# OnOnfre_DevBoard_rev4.net
KiCad netlist of a schematic drawn in EAGLE
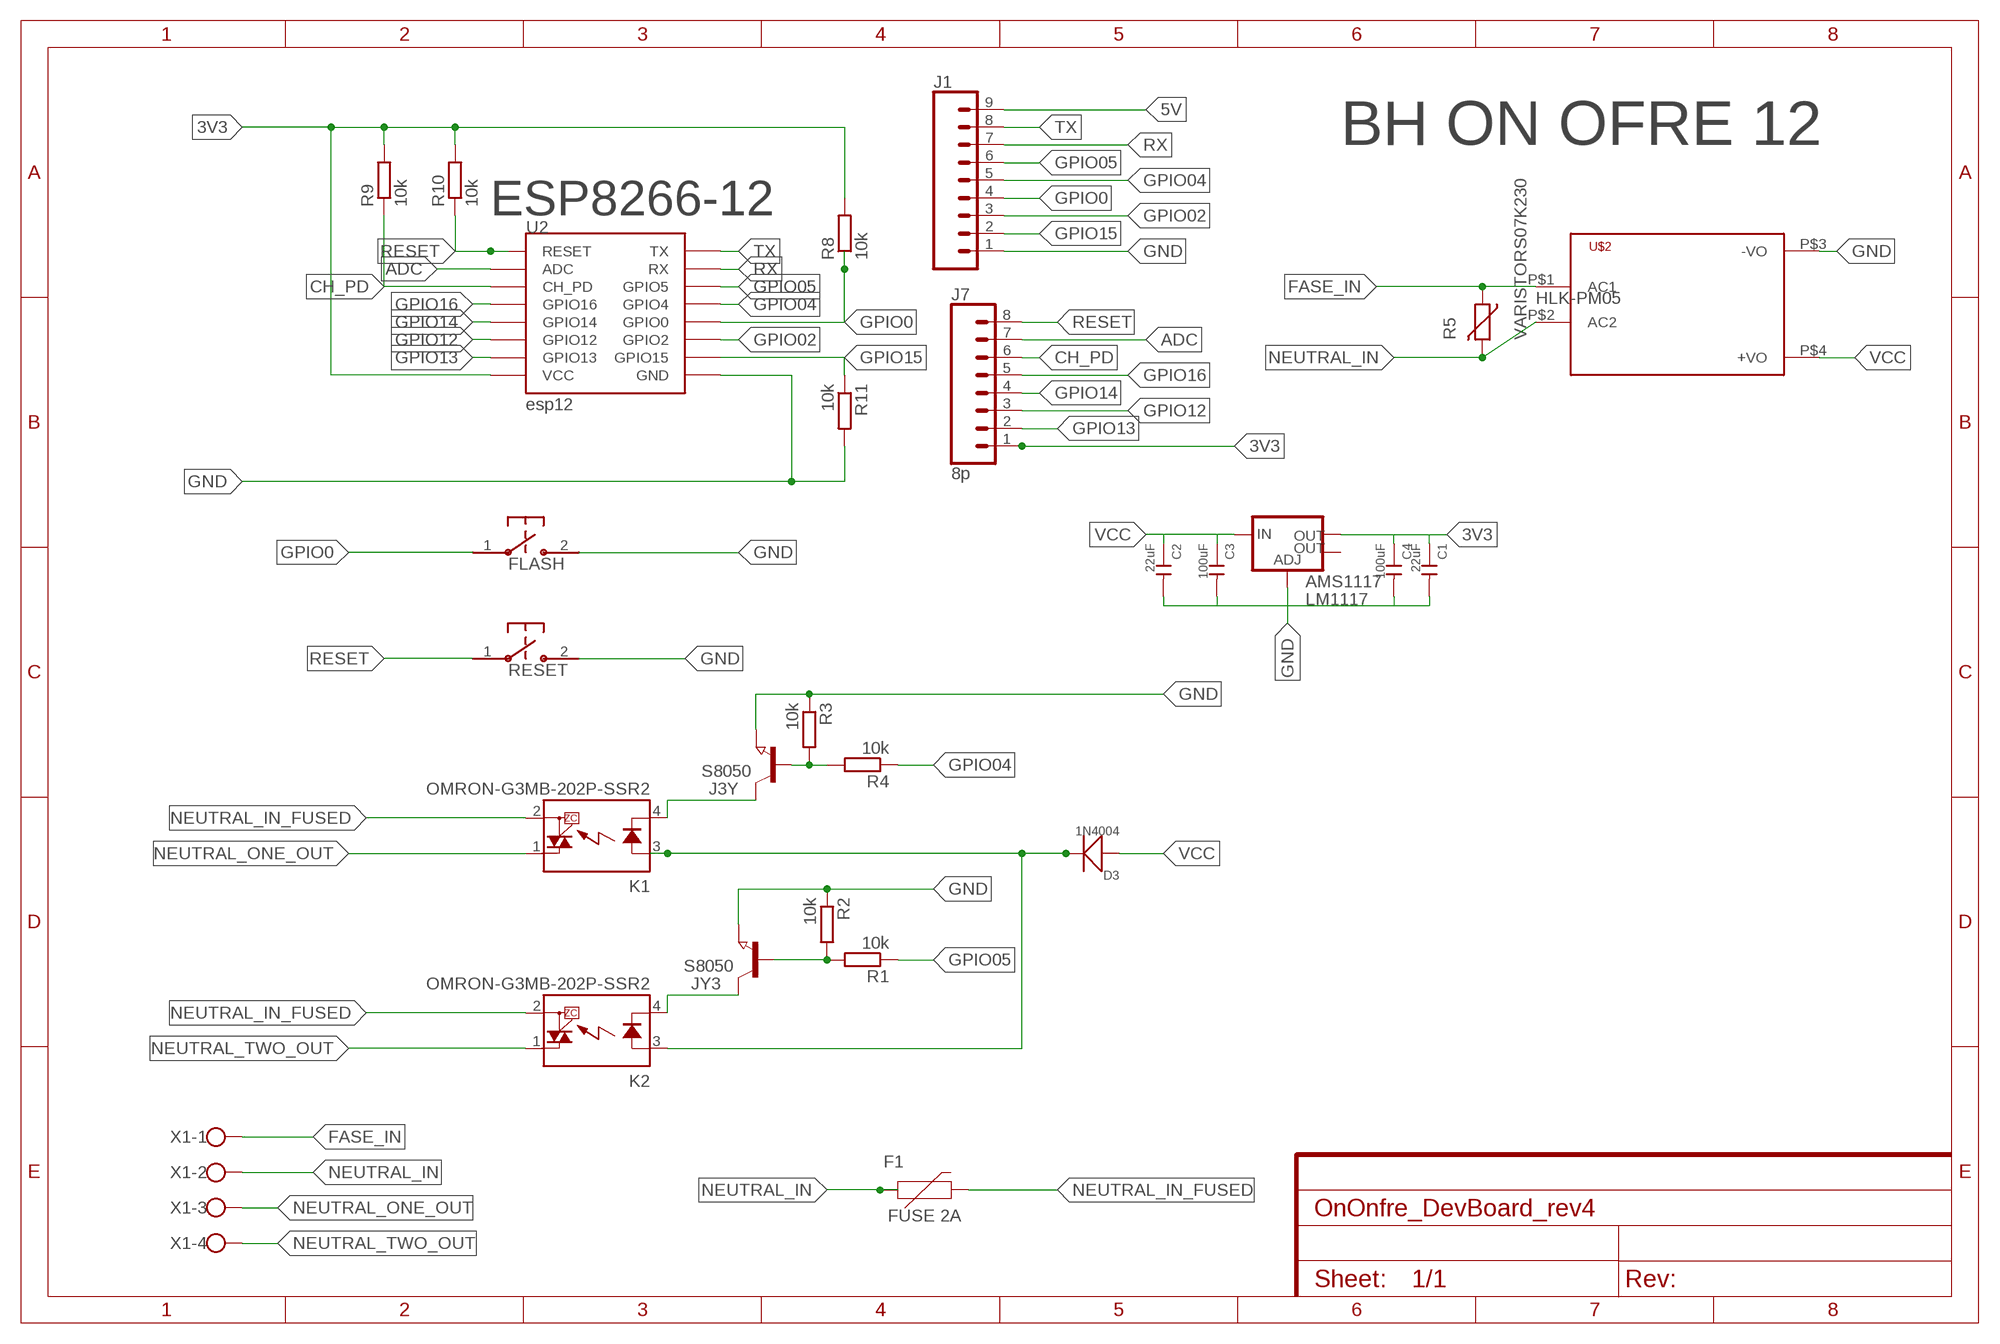
[diagram p0: schematic, sheet 1]

(export (version "E")
  (design (tool "Eeschema 10.0.6"))
  (components
    (comp (ref "AMS1117")
      (value "LM1117")
      (footprint "eagle-import:SOT223")
      (libsource (lib "eagle-import") (part "V_REG_LM1117SOT223"))
    )
    (comp (ref "C1")
      (value "22uF")
      (footprint "eagle-import:C1206")
      (fields (field (name "MPN") "CC1206KKX7RCBB102"))
      (libsource (lib "eagle-import") (part "CERAMIC-1NF-1KV-10%-X7R?(1206)"))
    )
    (comp (ref "C2")
      (value "22uF")
      (footprint "eagle-import:C1206")
      (fields (field (name "MPN") "CC1206KKX7RCBB102"))
      (libsource (lib "eagle-import") (part "CERAMIC-1NF-1KV-10%-X7R?(1206)"))
    )
    (comp (ref "C3")
      (value "100uF")
      (footprint "eagle-import:C1206")
      (fields (field (name "MPN") "CC1206KKX7RCBB102"))
      (libsource (lib "eagle-import") (part "CERAMIC-1NF-1KV-10%-X7R?(1206)"))
    )
    (comp (ref "C4")
      (value "100uF")
      (footprint "eagle-import:C1206")
      (fields (field (name "MPN") "CC1206KKX7RCBB102"))
      (libsource (lib "eagle-import") (part "CERAMIC-1NF-1KV-10%-X7R?(1206)"))
    )
    (comp (ref "D3")
      (value "1N4004")
      (footprint "eagle-import:DO-214AC")
      (fields (field (name "MPN") "1N4007"))
      (libsource (lib "eagle-import") (part "DIODE-GEN-PURPOSE-1KV-1A(DO-214AC)"))
    )
    (comp (ref "F1")
      (value "FUSE 2A")
      (footprint "eagle-import:PTH")
      (libsource (lib "eagle-import") (part "PPTC_PTH"))
    )
    (comp (ref "FLASH")
      (value "B3U-1000P-2P-SMD")
      (footprint "eagle-import:B3U-1000P")
      (fields (field (name "MANUFACTURER") "Omron") (field (name "MPN") "B3U-1000P"))
      (libsource (lib "eagle-import") (part "B3U-1000P"))
    )
    (comp (ref "J1")
      (value "CONN_09")
      (footprint "eagle-import:1X09")
      (libsource (lib "eagle-import") (part "CONN_09"))
    )
    (comp (ref "J3Y")
      (value "S8050")
      (footprint "eagle-import:SOT23")
      (libsource (lib "eagle-import") (part "NPN-TRANSISTOR_SOT23"))
    )
    (comp (ref "J7")
      (value "8p")
      (footprint "eagle-import:1X08")
      (libsource (lib "eagle-import") (part "CONN_08{dblquote}"))
    )
    (comp (ref "JY3")
      (value "S8050")
      (footprint "eagle-import:SOT23")
      (libsource (lib "eagle-import") (part "NPN-TRANSISTOR_SOT23"))
    )
    (comp (ref "K1")
      (value "OMRON-G3MB-202P-SSR2")
      (footprint "eagle-import:OMRON-G3MB-202P-SSR")
      (fields (field (name "MPN") "S202S02F"))
      (libsource (lib "eagle-import") (part "OMRON-G3MB-202P-SSR2"))
    )
    (comp (ref "K2")
      (value "OMRON-G3MB-202P-SSR2")
      (footprint "eagle-import:OMRON-G3MB-202P-SSR")
      (fields (field (name "MPN") "S202S02F"))
      (libsource (lib "eagle-import") (part "OMRON-G3MB-202P-SSR2"))
    )
    (comp (ref "R1")
      (value "10k")
      (footprint "eagle-import:R0603")
      (libsource (lib "eagle-import") (part "R-EU_R0603"))
    )
    (comp (ref "R2")
      (value "10k")
      (footprint "eagle-import:R0603")
      (libsource (lib "eagle-import") (part "R-EU_R0603"))
    )
    (comp (ref "R3")
      (value "10k")
      (footprint "eagle-import:R0603")
      (libsource (lib "eagle-import") (part "R-EU_R0603"))
    )
    (comp (ref "R4")
      (value "10k")
      (footprint "eagle-import:R0603")
      (libsource (lib "eagle-import") (part "R-EU_R0603"))
    )
    (comp (ref "R5")
      (value "VARISTORS07K230")
      (footprint "eagle-import:S07K230")
      (libsource (lib "eagle-import") (part "VARISTORS07K230"))
    )
    (comp (ref "R8")
      (value "10k")
      (footprint "eagle-import:R0603")
      (libsource (lib "eagle-import") (part "R-EU_R0603"))
    )
    (comp (ref "R9")
      (value "10k")
      (footprint "eagle-import:R0603")
      (libsource (lib "eagle-import") (part "R-EU_R0603"))
    )
    (comp (ref "R10")
      (value "10k")
      (footprint "eagle-import:R0603")
      (libsource (lib "eagle-import") (part "R-EU_R0603"))
    )
    (comp (ref "R11")
      (value "10k")
      (footprint "eagle-import:R0603")
      (libsource (lib "eagle-import") (part "R-EU_R0603"))
    )
    (comp (ref "RESET")
      (value "B3U-1000P-2P-SMD")
      (footprint "eagle-import:B3U-1000P")
      (fields (field (name "MANUFACTURER") "Omron") (field (name "MPN") "B3U-1000P"))
      (libsource (lib "eagle-import") (part "B3U-1000P"))
    )
    (comp (ref "U$2")
      (value "HKLPM01")
      (footprint "eagle-import:HKLPM01")
      (libsource (lib "eagle-import") (part "HKLPM01"))
    )
    (comp (ref "U2")
      (value "esp12")
      (footprint "eagle-import:ESP12-SMD")
      (libsource (lib "eagle-import") (part "ESP12SMD"))
    )
    (comp (ref "X1")
      (value "W237-4")
      (footprint "eagle-import:W237-4")
      (libsource (lib "eagle-import") (part "W237-4"))
    )
  )
  (nets
    (net (code "1") (name "3V3") (class "Default")
      (node (ref "AMS1117") (pin "2") (pinfunction "OUT_2") (pintype "output"))
      (node (ref "C1") (pin "1") (pinfunction "1_1") (pintype "passive"))
      (node (ref "C4") (pin "1") (pinfunction "1_1") (pintype "passive"))
      (node (ref "J7") (pin "1") (pinfunction "1_1") (pintype "passive"))
      (node (ref "R10") (pin "2") (pinfunction "2_2") (pintype "passive"))
      (node (ref "R8") (pin "2") (pinfunction "2_2") (pintype "passive"))
      (node (ref "R9") (pin "2") (pinfunction "2_2") (pintype "passive"))
      (node (ref "U2") (pin "VCC") (pinfunction "VCC_VCC") (pintype "bidirectional"))
    )
    (net (code "2") (name "5V") (class "Default")
      (node (ref "D3") (pin "2") (pinfunction "-_2") (pintype "passive"))
      (node (ref "J1") (pin "9") (pinfunction "9_9") (pintype "passive"))
      (node (ref "K1") (pin "3") (pinfunction "A_3") (pintype "passive"))
      (node (ref "K2") (pin "3") (pinfunction "A_3") (pintype "passive"))
    )
    (net (code "3") (name "ADC") (class "Default")
      (node (ref "J7") (pin "7") (pinfunction "7_7") (pintype "passive"))
      (node (ref "U2") (pin "ADC") (pinfunction "ADC_ADC") (pintype "bidirectional"))
    )
    (net (code "4") (name "CH_PD") (class "Default")
      (node (ref "J7") (pin "6") (pinfunction "6_6") (pintype "passive"))
      (node (ref "R9") (pin "1") (pinfunction "1_1") (pintype "passive"))
      (node (ref "U2") (pin "CH_PD") (pinfunction "CH_PD_CH_PD") (pintype "bidirectional"))
    )
    (net (code "5") (name "FASE_IN") (class "Default")
      (node (ref "R5") (pin "1") (pinfunction "1_1") (pintype "passive"))
      (node (ref "U$2") (pin "P$1") (pinfunction "AC1_P$1") (pintype "bidirectional"))
      (node (ref "X1") (pin "1") (pinfunction "KL_1") (pintype "passive"))
    )
    (net (code "6") (name "GND") (class "Default")
      (node (ref "AMS1117") (pin "1") (pinfunction "ADJ_1") (pintype "input"))
      (node (ref "C1") (pin "2") (pinfunction "2_2") (pintype "passive"))
      (node (ref "C2") (pin "2") (pinfunction "2_2") (pintype "passive"))
      (node (ref "C3") (pin "2") (pinfunction "2_2") (pintype "passive"))
      (node (ref "C4") (pin "2") (pinfunction "2_2") (pintype "passive"))
      (node (ref "FLASH") (pin "2") (pinfunction "P$2_2") (pintype "passive"))
      (node (ref "J1") (pin "1") (pinfunction "1_1") (pintype "passive"))
      (node (ref "J3Y") (pin "2") (pinfunction "E_2") (pintype "passive"))
      (node (ref "JY3") (pin "2") (pinfunction "E_2") (pintype "passive"))
      (node (ref "R11") (pin "2") (pinfunction "2_2") (pintype "passive"))
      (node (ref "R2") (pin "1") (pinfunction "1_1") (pintype "passive"))
      (node (ref "R3") (pin "1") (pinfunction "1_1") (pintype "passive"))
      (node (ref "RESET") (pin "2") (pinfunction "P$2_2") (pintype "passive"))
      (node (ref "U$2") (pin "P$3") (pinfunction "-VO_P$3") (pintype "bidirectional"))
      (node (ref "U2") (pin "GND") (pinfunction "GND_GND") (pintype "bidirectional"))
    )
    (net (code "7") (name "GPIO0") (class "Default")
      (node (ref "FLASH") (pin "1") (pinfunction "P$1_1") (pintype "passive"))
      (node (ref "J1") (pin "4") (pinfunction "4_4") (pintype "passive"))
      (node (ref "R8") (pin "1") (pinfunction "1_1") (pintype "passive"))
      (node (ref "U2") (pin "GPIO0") (pinfunction "GPIO0_GPIO0") (pintype "bidirectional"))
    )
    (net (code "8") (name "GPIO02") (class "Default")
      (node (ref "J1") (pin "3") (pinfunction "3_3") (pintype "passive"))
      (node (ref "U2") (pin "GPIO2") (pinfunction "GPIO2_GPIO2") (pintype "bidirectional"))
    )
    (net (code "9") (name "GPIO04") (class "Default")
      (node (ref "J1") (pin "5") (pinfunction "5_5") (pintype "passive"))
      (node (ref "R4") (pin "1") (pinfunction "1_1") (pintype "passive"))
      (node (ref "U2") (pin "GPIO4") (pinfunction "GPIO4_GPIO4") (pintype "bidirectional"))
    )
    (net (code "10") (name "GPIO05") (class "Default")
      (node (ref "J1") (pin "6") (pinfunction "6_6") (pintype "passive"))
      (node (ref "R1") (pin "1") (pinfunction "1_1") (pintype "passive"))
      (node (ref "U2") (pin "GPIO5") (pinfunction "GPIO5_GPIO5") (pintype "bidirectional"))
    )
    (net (code "11") (name "GPIO12") (class "Default")
      (node (ref "J7") (pin "3") (pinfunction "3_3") (pintype "passive"))
      (node (ref "U2") (pin "GPIO12") (pinfunction "GPIO12_GPIO12") (pintype "bidirectional"))
    )
    (net (code "12") (name "GPIO13") (class "Default")
      (node (ref "J7") (pin "2") (pinfunction "2_2") (pintype "passive"))
      (node (ref "U2") (pin "GPIO13") (pinfunction "GPIO13_GPIO13") (pintype "bidirectional"))
    )
    (net (code "13") (name "GPIO14") (class "Default")
      (node (ref "J7") (pin "4") (pinfunction "4_4") (pintype "passive"))
      (node (ref "U2") (pin "GPIO14") (pinfunction "GPIO14_GPIO14") (pintype "bidirectional"))
    )
    (net (code "14") (name "GPIO15") (class "Default")
      (node (ref "J1") (pin "2") (pinfunction "2_2") (pintype "passive"))
      (node (ref "R11") (pin "1") (pinfunction "1_1") (pintype "passive"))
      (node (ref "U2") (pin "GPIO15") (pinfunction "GPIO15_GPIO15") (pintype "bidirectional"))
    )
    (net (code "15") (name "GPIO16") (class "Default")
      (node (ref "J7") (pin "5") (pinfunction "5_5") (pintype "passive"))
      (node (ref "U2") (pin "GPIO16") (pinfunction "GPIO16_GPIO16") (pintype "bidirectional"))
    )
    (net (code "16") (name "NEUTRAL_IN") (class "Default")
      (node (ref "F1") (pin "P$1") (pinfunction "1_P$1") (pintype "bidirectional"))
      (node (ref "R5") (pin "2") (pinfunction "2_2") (pintype "passive"))
      (node (ref "U$2") (pin "P$2") (pinfunction "AC2_P$2") (pintype "bidirectional"))
      (node (ref "X1") (pin "2") (pinfunction "KL_2") (pintype "passive"))
    )
    (net (code "17") (name "NEUTRAL_IN_FUSED") (class "Default")
      (node (ref "F1") (pin "P$2") (pinfunction "2_P$2") (pintype "bidirectional"))
      (node (ref "K1") (pin "2") (pinfunction "DS2_2") (pintype "passive"))
      (node (ref "K2") (pin "2") (pinfunction "DS2_2") (pintype "passive"))
    )
    (net (code "18") (name "NEUTRAL_ONE_OUT") (class "Default")
      (node (ref "K1") (pin "1") (pinfunction "DS1_1") (pintype "passive"))
      (node (ref "X1") (pin "3") (pinfunction "KL_3") (pintype "passive"))
    )
    (net (code "19") (name "NEUTRAL_TWO_OUT") (class "Default")
      (node (ref "K2") (pin "1") (pinfunction "DS1_1") (pintype "passive"))
      (node (ref "X1") (pin "4") (pinfunction "KL_4") (pintype "passive"))
    )
    (net (code "20") (name "Net-(J3Y-B)") (class "Default")
      (node (ref "J3Y") (pin "1") (pinfunction "B_1") (pintype "passive"))
      (node (ref "R3") (pin "2") (pinfunction "2_2") (pintype "passive"))
      (node (ref "R4") (pin "2") (pinfunction "2_2") (pintype "passive"))
    )
    (net (code "21") (name "Net-(J3Y-C)") (class "Default")
      (node (ref "J3Y") (pin "3") (pinfunction "C_3") (pintype "passive"))
      (node (ref "K1") (pin "4") (pinfunction "K_4") (pintype "passive"))
    )
    (net (code "22") (name "Net-(JY3-B)") (class "Default")
      (node (ref "JY3") (pin "1") (pinfunction "B_1") (pintype "passive"))
      (node (ref "R1") (pin "2") (pinfunction "2_2") (pintype "passive"))
      (node (ref "R2") (pin "2") (pinfunction "2_2") (pintype "passive"))
    )
    (net (code "23") (name "Net-(JY3-C)") (class "Default")
      (node (ref "JY3") (pin "3") (pinfunction "C_3") (pintype "passive"))
      (node (ref "K2") (pin "4") (pinfunction "K_4") (pintype "passive"))
    )
    (net (code "24") (name "RESET") (class "Default")
      (node (ref "J7") (pin "8") (pinfunction "8_8") (pintype "passive"))
      (node (ref "R10") (pin "1") (pinfunction "1_1") (pintype "passive"))
      (node (ref "RESET") (pin "1") (pinfunction "P$1_1") (pintype "passive"))
      (node (ref "U2") (pin "RESET") (pinfunction "RESET_RESET") (pintype "bidirectional"))
    )
    (net (code "25") (name "RX") (class "Default")
      (node (ref "J1") (pin "7") (pinfunction "7_7") (pintype "passive"))
      (node (ref "U2") (pin "RXD0") (pinfunction "RX_RXD0") (pintype "bidirectional"))
    )
    (net (code "26") (name "TX") (class "Default")
      (node (ref "J1") (pin "8") (pinfunction "8_8") (pintype "passive"))
      (node (ref "U2") (pin "TXD0") (pinfunction "TX_TXD0") (pintype "bidirectional"))
    )
    (net (code "27") (name "VCC") (class "Default")
      (node (ref "AMS1117") (pin "3") (pinfunction "IN_3") (pintype "input"))
      (node (ref "C2") (pin "1") (pinfunction "1_1") (pintype "passive"))
      (node (ref "C3") (pin "1") (pinfunction "1_1") (pintype "passive"))
      (node (ref "D3") (pin "1") (pinfunction "+_1") (pintype "passive"))
      (node (ref "U$2") (pin "P$4") (pinfunction "+VO_P$4") (pintype "bidirectional"))
    )
    (net (code "28") (name "unconnected-(AMS1117-OUT-Pad4)") (class "Default")
      (node (ref "AMS1117") (pin "4") (pinfunction "OUT_4") (pintype "output"))
    )
  )
)
